# MCU.net
KiCad netlist of a schematic drawn in Altium Designer
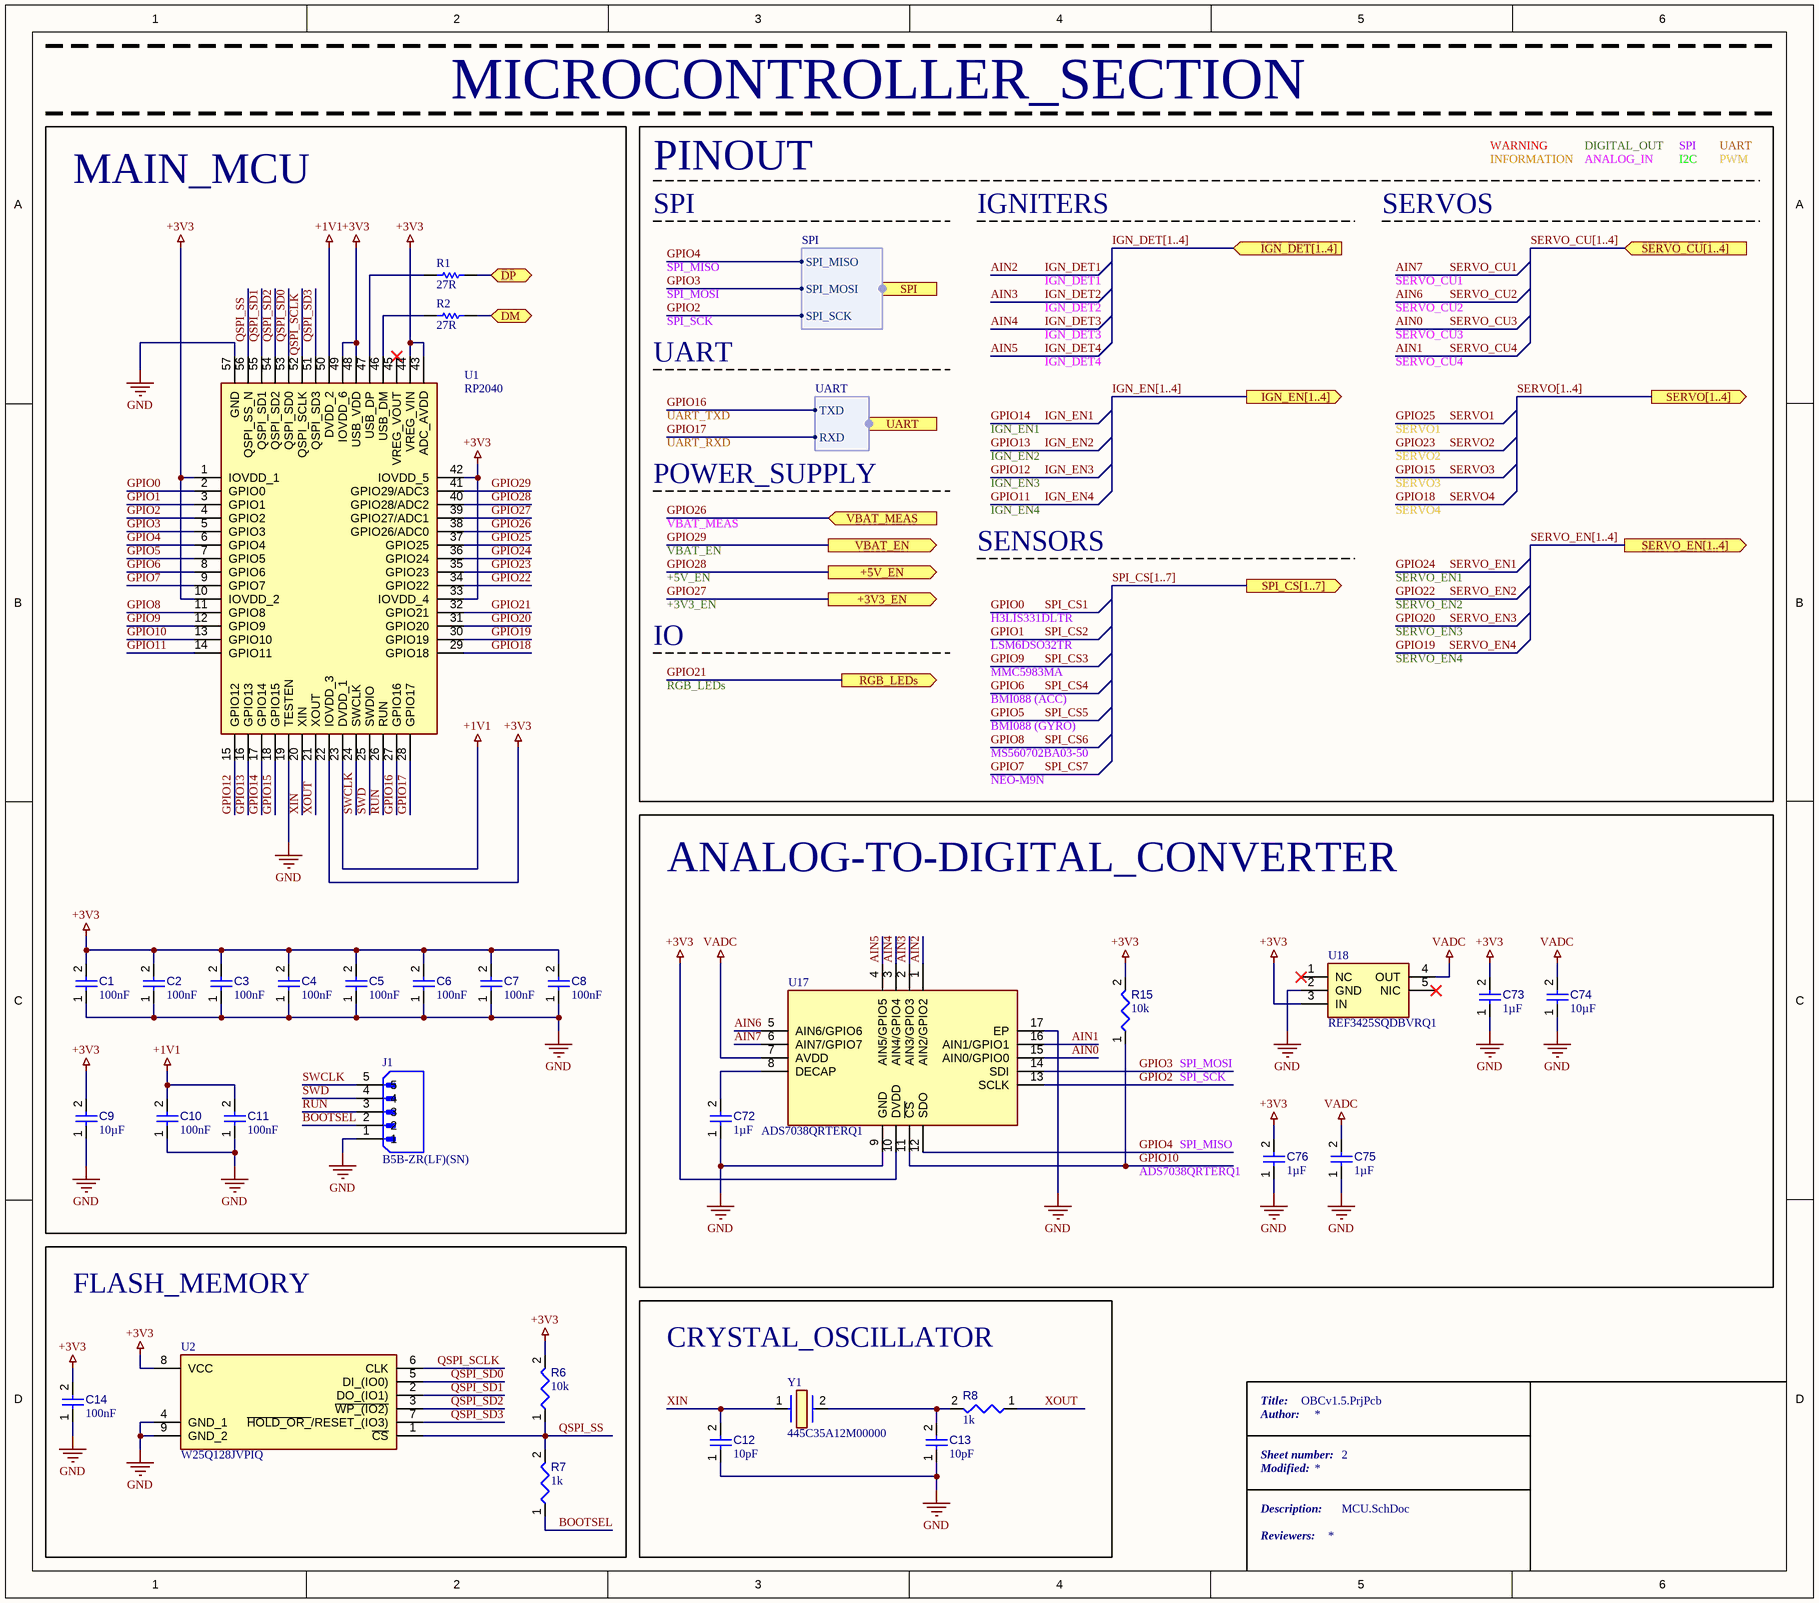
[diagram p0: MCU.SchDoc]

(export (version "E")
  (design (tool "Eeschema 10.0.6"))
  (components
    (comp (ref "C1")
      (value "100nF")
      (footprint "CAPC0402(1005)60_L")
      (description "Chip Capacitor, 100nF +/-20%, 10V, 0402, Thickness 0.6 mm")
      (fields (field (name "TOLERANCE") "20%") (field (name "Comment") "Capacitor 100nF +/-20% 10V 0402"))
      (libsource (lib "PWr in Space team") (part "CAP-NP-2"))
    )
    (comp (ref "C2")
      (value "100nF")
      (footprint "CAPC0402(1005)60_L")
      (description "Chip Capacitor, 100nF +/-20%, 10V, 0402, Thickness 0.6 mm")
      (fields (field (name "TOLERANCE") "20%") (field (name "Comment") "Capacitor 100nF +/-20% 10V 0402"))
      (libsource (lib "PWr in Space team") (part "CAP-NP-2"))
    )
    (comp (ref "C3")
      (value "100nF")
      (footprint "CAPC0402(1005)60_L")
      (description "Chip Capacitor, 100nF +/-20%, 10V, 0402, Thickness 0.6 mm")
      (fields (field (name "TOLERANCE") "20%") (field (name "Comment") "Capacitor 100nF +/-20% 10V 0402"))
      (libsource (lib "PWr in Space team") (part "CAP-NP-2"))
    )
    (comp (ref "C4")
      (value "100nF")
      (footprint "CAPC0402(1005)60_L")
      (description "Chip Capacitor, 100nF +/-20%, 10V, 0402, Thickness 0.6 mm")
      (fields (field (name "TOLERANCE") "20%") (field (name "Comment") "Capacitor 100nF +/-20% 10V 0402"))
      (libsource (lib "PWr in Space team") (part "CAP-NP-2"))
    )
    (comp (ref "C5")
      (value "100nF")
      (footprint "CAPC0402(1005)60_L")
      (description "Chip Capacitor, 100nF +/-20%, 10V, 0402, Thickness 0.6 mm")
      (fields (field (name "TOLERANCE") "20%") (field (name "Comment") "Capacitor 100nF +/-20% 10V 0402"))
      (libsource (lib "PWr in Space team") (part "CAP-NP-2"))
    )
    (comp (ref "C6")
      (value "100nF")
      (footprint "CAPC0402(1005)60_L")
      (description "Chip Capacitor, 100nF +/-20%, 10V, 0402, Thickness 0.6 mm")
      (fields (field (name "TOLERANCE") "20%") (field (name "Comment") "Capacitor 100nF +/-20% 10V 0402"))
      (libsource (lib "PWr in Space team") (part "CAP-NP-2"))
    )
    (comp (ref "C7")
      (value "100nF")
      (footprint "CAPC0402(1005)60_L")
      (description "Chip Capacitor, 100nF +/-20%, 10V, 0402, Thickness 0.6 mm")
      (fields (field (name "TOLERANCE") "20%") (field (name "Comment") "Capacitor 100nF +/-20% 10V 0402"))
      (libsource (lib "PWr in Space team") (part "CAP-NP-2"))
    )
    (comp (ref "C8")
      (value "100nF")
      (footprint "CAPC0402(1005)60_L")
      (description "Chip Capacitor, 100nF +/-20%, 10V, 0402, Thickness 0.6 mm")
      (fields (field (name "TOLERANCE") "20%") (field (name "Comment") "Capacitor 100nF +/-20% 10V 0402"))
      (libsource (lib "PWr in Space team") (part "CAP-NP-2"))
    )
    (comp (ref "C9")
      (value "10µF")
      (footprint "CAPC3216X180X50NL20T25")
      (description "Chip Capacitor, 10 uF, +/- 10%, 16 V, 1206 (3216 Metric)")
      (fields (field (name "TOLERANCE") "10%") (field (name "Comment") "Capacitor 10 uF +/- 10% 16 V 1206"))
      (libsource (lib "PWr in Space team") (part "CAP-NP-2"))
    )
    (comp (ref "C10")
      (value "100nF")
      (footprint "CAPC0402(1005)60_L")
      (description "Chip Capacitor, 100nF +/-20%, 10V, 0402, Thickness 0.6 mm")
      (fields (field (name "TOLERANCE") "20%") (field (name "Comment") "Capacitor 100nF +/-20% 10V 0402"))
      (libsource (lib "PWr in Space team") (part "CAP-NP-2"))
    )
    (comp (ref "C11")
      (value "100nF")
      (footprint "CAPC0402(1005)60_L")
      (description "Chip Capacitor, 100nF +/-20%, 10V, 0402, Thickness 0.6 mm")
      (fields (field (name "TOLERANCE") "20%") (field (name "Comment") "Capacitor 100nF +/-20% 10V 0402"))
      (libsource (lib "PWr in Space team") (part "CAP-NP-2"))
    )
    (comp (ref "C12")
      (value "10pF")
      (footprint "CAPC1005X55X30LL05T10")
      (description "Chip Capacitor, 10 pF, +/- 0.25 pF, 50 V, 0402 (1005 Metric)")
      (fields
        (field (name "TOLERANCE") "0.25%")
        (field (name "Comment") "Capacitor 10 pF +/- 0.25 pF 50 V 0402")
      )
      (libsource (lib "PWr in Space team") (part "CAP-NP-2"))
    )
    (comp (ref "C13")
      (value "10pF")
      (footprint "CAPC1005X55X30LL05T10")
      (description "Chip Capacitor, 10 pF, +/- 0.25 pF, 50 V, 0402 (1005 Metric)")
      (fields
        (field (name "TOLERANCE") "0.25%")
        (field (name "Comment") "Capacitor 10 pF +/- 0.25 pF 50 V 0402")
      )
      (libsource (lib "PWr in Space team") (part "CAP-NP-2"))
    )
    (comp (ref "C14")
      (value "100nF")
      (footprint "CAPC0402(1005)60_L")
      (description "Chip Capacitor, 100nF +/-20%, 10V, 0402, Thickness 0.6 mm")
      (fields (field (name "TOLERANCE") "20%") (field (name "Comment") "Capacitor 100nF +/-20% 10V 0402"))
      (libsource (lib "PWr in Space team") (part "CAP-NP-2"))
    )
    (comp (ref "C72")
      (value "1µF")
      (footprint "CAPC0402(1005)60_L")
      (description "Chip Capacitor, 1µF +/-20%, 10V, 0402, Thickness 0.6 mm")
      (fields (field (name "TOLERANCE") "10%") (field (name "Comment") "Capacitor 1µF +/-20% 10V 0402"))
      (libsource (lib "PWr in Space team") (part "CAP-NP-2"))
    )
    (comp (ref "C73")
      (value "1µF")
      (footprint "CAPC0402(1005)60_L")
      (description "Chip Capacitor, 1µF +/-20%, 10V, 0402, Thickness 0.6 mm")
      (fields (field (name "TOLERANCE") "10%") (field (name "Comment") "Capacitor 1µF +/-20% 10V 0402"))
      (libsource (lib "PWr in Space team") (part "CAP-NP-2"))
    )
    (comp (ref "C74")
      (value "10µF")
      (footprint "CAPC0603(1608)100_L")
      (description "Chip Capacitor, 10µF +/-20%, 10V, 0603, Thickness 1 mm")
      (fields (field (name "TOLERANCE") "10%") (field (name "Comment") "Capacitor 10µF +/-20% 10V 0603"))
      (libsource (lib "PWr in Space team") (part "CAP-NP-2"))
    )
    (comp (ref "C75")
      (value "1µF")
      (footprint "CAPC0402(1005)60_L")
      (description "Chip Capacitor, 1µF +/-20%, 10V, 0402, Thickness 0.6 mm")
      (fields (field (name "TOLERANCE") "10%") (field (name "Comment") "Capacitor 1µF +/-20% 10V 0402"))
      (libsource (lib "PWr in Space team") (part "CAP-NP-2"))
    )
    (comp (ref "C76")
      (value "1µF")
      (footprint "CAPC0402(1005)60_L")
      (description "Chip Capacitor, 1µF +/-20%, 10V, 0402, Thickness 0.6 mm")
      (fields (field (name "TOLERANCE") "10%") (field (name "Comment") "Capacitor 1µF +/-20% 10V 0402"))
      (libsource (lib "PWr in Space team") (part "CAP-NP-2"))
    )
    (comp (ref "J1")
      (value "B5B-ZR(LF)(SN)")
      (footprint "JST_B5B-ZR(LF)(SN)")
      (fields (field (name "MF") "{'manufacturer': u'JST'}"))
      (libsource (lib "SnapEDA_Library") (part "B5B-ZR(LF)(SN)"))
    )
    (comp (ref "R1")
      (value "27R")
      (footprint "RESC1005X40X25NL05T05")
      (fields (field (name "MANUFACTURER") "Vishay Dale") (field (name "PART NUMBER") "CRCW040227R0JNED"))
      (libsource (lib "Altium Content Vault") (part "RES"))
    )
    (comp (ref "R2")
      (value "27R")
      (footprint "RESC1005X40X25NL05T05")
      (fields (field (name "MANUFACTURER") "Vishay Dale") (field (name "PART NUMBER") "CRCW040227R0JNED"))
      (libsource (lib "Altium Content Vault") (part "RES"))
    )
    (comp (ref "R6")
      (value "10k")
      (footprint "RESC0402(1005)_L")
      (description "Chip Resistor, 10 kOhms, +/-1 %, 63 mW, -55 to 125 degC, 0402")
      (fields (field (name "POWER") "63mW") (field (name "TOLERANCE") "1%"))
      (libsource (lib "PWr in Space team") (part "RES-2"))
    )
    (comp (ref "R7")
      (value "1k")
      (footprint "RESC0402(1005)_L")
      (description "Chip Resistor, 1 kOhms, +/-5 %, 63 mW, -55 to 155 degC, 0402")
      (fields (field (name "TOLERANCE") "5%") (field (name "POWER") "63mW"))
      (libsource (lib "PWr in Space team") (part "RES-2"))
    )
    (comp (ref "R8")
      (value "1k")
      (footprint "RESC0402(1005)_L")
      (description "Chip Resistor, 1 kOhms, +/-5 %, 63 mW, -55 to 155 degC, 0402")
      (fields (field (name "TOLERANCE") "5%") (field (name "POWER") "63mW"))
      (libsource (lib "PWr in Space team") (part "RES-2"))
    )
    (comp (ref "R15")
      (value "10k")
      (footprint "RESC0402(1005)_L")
      (description "Chip Resistor, 10 kOhms, +/-1 %, 63 mW, -55 to 125 degC, 0402")
      (fields (field (name "POWER") "63mW") (field (name "TOLERANCE") "1%"))
      (libsource (lib "PWr in Space team") (part "RES-2"))
    )
    (comp (ref "U1")
      (value "RP2040")
      (footprint "QFN40P700X700X90-57N-D")
      (description "Integrated Circuit")
      (fields
        (field (name "MANUFACTURER_PART_NUMBER") "RPI Chip RP2040-10-10")
        (field (name "MOUSER PART NUMBER") "358-RP2040CHIP-10-10")
      )
      (libsource (lib "PWr in Space team") (part "RPI_Chip_RP2040-10-10"))
    )
    (comp (ref "U2")
      (value "W25Q128JVPIQ")
      (footprint "SamacSys:SON127P600X500X80-9N-D")
      (description "Integrated Circuit")
      (fields (field (name "MOUSER PART NUMBER") "454-W25Q128JVPIQ"))
      (libsource (lib "*") (part "W25Q128JVPIQ"))
    )
    (comp (ref "U17")
      (value "ADS7038QRTERQ1")
      (footprint "SamacSys:QFN50P300X300X80-17N-D")
      (description "Integrated Circuit")
      (fields (field (name "MOUSER PART NUMBER") "595-ADS7038QRTERQ1"))
      (libsource (lib "*") (part "ADS7038QRTERQ1"))
    )
    (comp (ref "U18")
      (value "REF3425SQDBVRQ1")
      (footprint "SamacSys:SOT95P280X145-5N")
      (description "Integrated Circuit")
      (fields (field (name "MOUSER PART NUMBER") "595-REF3425SQDBVRQ1"))
      (libsource (lib "*") (part "REF3425SQDBVRQ1"))
    )
    (comp (ref "Y1")
      (value "445C35A12M00000")
      (footprint "SamacSys:445I23D24M00000")
      (description "Crystal or Oscillator")
      (fields
        (field (name "MANUFACTURER_PART_NUMBER") "445I23D12M00000")
        (field (name "MOUSER PART NUMBER") "774-445I23D12M00000")
      )
      (libsource (lib "*") (part "445I23D12M00000"))
    )
  )
  (nets
    (net (code "3") (name "+1V1") (class "Default")
      (node (ref "C10") (pin "2") (pinfunction "2_2") (pintype "passive"))
      (node (ref "C11") (pin "2") (pinfunction "2_2") (pintype "passive"))
      (node (ref "U1") (pin "23") (pinfunction "DVDD_1_23") (pintype "passive"))
      (node (ref "U1") (pin "50") (pinfunction "DVDD_2_50") (pintype "passive"))
    )
    (net (code "4") (name "+3V3") (class "Default")
      (node (ref "C1") (pin "2") (pinfunction "2_2") (pintype "passive"))
      (node (ref "C14") (pin "2") (pinfunction "2_2") (pintype "passive"))
      (node (ref "C2") (pin "2") (pinfunction "2_2") (pintype "passive"))
      (node (ref "C3") (pin "2") (pinfunction "2_2") (pintype "passive"))
      (node (ref "C4") (pin "2") (pinfunction "2_2") (pintype "passive"))
      (node (ref "C5") (pin "2") (pinfunction "2_2") (pintype "passive"))
      (node (ref "C6") (pin "2") (pinfunction "2_2") (pintype "passive"))
      (node (ref "C7") (pin "2") (pinfunction "2_2") (pintype "passive"))
      (node (ref "C73") (pin "2") (pinfunction "2_2") (pintype "passive"))
      (node (ref "C76") (pin "2") (pinfunction "2_2") (pintype "passive"))
      (node (ref "C8") (pin "2") (pinfunction "2_2") (pintype "passive"))
      (node (ref "C9") (pin "2") (pinfunction "2_2") (pintype "passive"))
      (node (ref "R15") (pin "2") (pinfunction "2_2") (pintype "passive"))
      (node (ref "R6") (pin "2") (pinfunction "2_2") (pintype "passive"))
      (node (ref "U1") (pin "1") (pinfunction "IOVDD_1_1") (pintype "passive"))
      (node (ref "U1") (pin "10") (pinfunction "IOVDD_2_10") (pintype "passive"))
      (node (ref "U1") (pin "22") (pinfunction "IOVDD_3_22") (pintype "passive"))
      (node (ref "U1") (pin "33") (pinfunction "IOVDD_4_33") (pintype "passive"))
      (node (ref "U1") (pin "42") (pinfunction "IOVDD_5_42") (pintype "passive"))
      (node (ref "U1") (pin "43") (pinfunction "ADC_AVDD_43") (pintype "passive"))
      (node (ref "U1") (pin "44") (pinfunction "VREG_VIN_44") (pintype "passive"))
      (node (ref "U1") (pin "48") (pinfunction "USB_VDD_48") (pintype "passive"))
      (node (ref "U1") (pin "49") (pinfunction "IOVDD_6_49") (pintype "passive"))
      (node (ref "U17") (pin "10") (pinfunction "DVDD_10") (pintype "passive"))
      (node (ref "U18") (pin "3") (pinfunction "IN_3") (pintype "passive"))
      (node (ref "U2") (pin "8") (pinfunction "VCC_8") (pintype "passive"))
    )
    (net (code "5") (name "/BOOTSEL") (class "Default")
      (node (ref "J1") (pin "2") (pinfunction "2_2") (pintype "passive"))
      (node (ref "R7") (pin "1") (pinfunction "1_1") (pintype "passive"))
    )
    (net (code "6") (name "/DM") (class "Default")
      (node (ref "R2") (pin "2") (pinfunction "2_2") (pintype "passive"))
    )
    (net (code "7") (name "/DP") (class "Default")
      (node (ref "R1") (pin "2") (pinfunction "2_2") (pintype "passive"))
    )
    (net (code "8") (name "/GPIO2") (class "Default")
      (node (ref "U1") (pin "4") (pinfunction "GPIO2_4") (pintype "passive"))
      (node (ref "U17") (pin "13") (pinfunction "SCLK_13") (pintype "passive"))
    )
    (net (code "9") (name "/GPIO3") (class "Default")
      (node (ref "U1") (pin "5") (pinfunction "GPIO3_5") (pintype "passive"))
      (node (ref "U17") (pin "14") (pinfunction "SDI_14") (pintype "passive"))
    )
    (net (code "10") (name "/GPIO4") (class "Default")
      (node (ref "U1") (pin "6") (pinfunction "GPIO4_6") (pintype "passive"))
      (node (ref "U17") (pin "12") (pinfunction "SDO_12") (pintype "passive"))
    )
    (net (code "11") (name "/GPIO10") (class "Default")
      (node (ref "R15") (pin "1") (pinfunction "1_1") (pintype "passive"))
      (node (ref "U1") (pin "13") (pinfunction "GPIO10_13") (pintype "passive"))
      (node (ref "U17") (pin "11") (pinfunction "~{CS}_11") (pintype "passive"))
    )
    (net (code "12") (name "/GPIO16") (class "Default")
      (node (ref "U1") (pin "27") (pinfunction "GPIO16_27") (pintype "passive"))
    )
    (net (code "13") (name "/GPIO17") (class "Default")
      (node (ref "U1") (pin "28") (pinfunction "GPIO17_28") (pintype "passive"))
    )
    (net (code "14") (name "/GPIO21") (class "Default")
      (node (ref "U1") (pin "32") (pinfunction "GPIO21_32") (pintype "passive"))
    )
    (net (code "15") (name "/GPIO26") (class "Default")
      (node (ref "U1") (pin "38") (pinfunction "GPIO26/ADC0_38") (pintype "passive"))
    )
    (net (code "16") (name "/GPIO27") (class "Default")
      (node (ref "U1") (pin "39") (pinfunction "GPIO27/ADC1_39") (pintype "passive"))
    )
    (net (code "17") (name "/GPIO28") (class "Default")
      (node (ref "U1") (pin "40") (pinfunction "GPIO28/ADC2_40") (pintype "passive"))
    )
    (net (code "18") (name "/GPIO29") (class "Default")
      (node (ref "U1") (pin "41") (pinfunction "GPIO29/ADC3_41") (pintype "passive"))
    )
    (net (code "19") (name "/IGN_DET1") (class "Default")
      (node (ref "U17") (pin "1") (pinfunction "AIN2/GPIO2_1") (pintype "passive"))
    )
    (net (code "20") (name "/IGN_DET2") (class "Default")
      (node (ref "U17") (pin "2") (pinfunction "AIN3/GPIO3_2") (pintype "passive"))
    )
    (net (code "21") (name "/IGN_DET3") (class "Default")
      (node (ref "U17") (pin "3") (pinfunction "AIN4/GPIO4_3") (pintype "passive"))
    )
    (net (code "22") (name "/IGN_DET4") (class "Default")
      (node (ref "U17") (pin "4") (pinfunction "AIN5/GPIO5_4") (pintype "passive"))
    )
    (net (code "24") (name "/IGN_EN1") (class "Default")
      (node (ref "U1") (pin "17") (pinfunction "GPIO14_17") (pintype "passive"))
    )
    (net (code "25") (name "/IGN_EN2") (class "Default")
      (node (ref "U1") (pin "16") (pinfunction "GPIO13_16") (pintype "passive"))
    )
    (net (code "26") (name "/IGN_EN3") (class "Default")
      (node (ref "U1") (pin "15") (pinfunction "GPIO12_15") (pintype "passive"))
    )
    (net (code "27") (name "/IGN_EN4") (class "Default")
      (node (ref "U1") (pin "14") (pinfunction "GPIO11_14") (pintype "passive"))
    )
    (net (code "29") (name "/QSPI_SCLK") (class "Default")
      (node (ref "U1") (pin "52") (pinfunction "QSPI_SCLK_52") (pintype "passive"))
      (node (ref "U2") (pin "6") (pinfunction "CLK_6") (pintype "passive"))
    )
    (net (code "30") (name "/QSPI_SD0") (class "Default")
      (node (ref "U1") (pin "53") (pinfunction "QSPI_SD0_53") (pintype "passive"))
      (node (ref "U2") (pin "5") (pinfunction "DI_(IO0)_5") (pintype "passive"))
    )
    (net (code "31") (name "/QSPI_SD1") (class "Default")
      (node (ref "U1") (pin "55") (pinfunction "QSPI_SD1_55") (pintype "passive"))
      (node (ref "U2") (pin "2") (pinfunction "DO_(IO1)_2") (pintype "passive"))
    )
    (net (code "32") (name "/QSPI_SD2") (class "Default")
      (node (ref "U1") (pin "54") (pinfunction "QSPI_SD2_54") (pintype "passive"))
      (node (ref "U2") (pin "3") (pinfunction "~{WP_(IO2)}_3") (pintype "passive"))
    )
    (net (code "33") (name "/QSPI_SD3") (class "Default")
      (node (ref "U1") (pin "51") (pinfunction "QSPI_SD3_51") (pintype "passive"))
      (node (ref "U2") (pin "7") (pinfunction "~{HOLD_OR_}/RESET_(IO3)_7") (pintype "passive"))
    )
    (net (code "34") (name "/QSPI_SS") (class "Default")
      (node (ref "R6") (pin "1") (pinfunction "1_1") (pintype "passive"))
      (node (ref "R7") (pin "2") (pinfunction "2_2") (pintype "passive"))
      (node (ref "U1") (pin "56") (pinfunction "QSPI_SS_N_56") (pintype "passive"))
      (node (ref "U2") (pin "1") (pinfunction "~{CS}_1") (pintype "passive"))
    )
    (net (code "35") (name "/RUN") (class "Default")
      (node (ref "J1") (pin "3") (pinfunction "3_3") (pintype "passive"))
      (node (ref "U1") (pin "26") (pinfunction "RUN_26") (pintype "passive"))
    )
    (net (code "36") (name "/SERVO1") (class "Default")
      (node (ref "U1") (pin "37") (pinfunction "GPIO25_37") (pintype "passive"))
    )
    (net (code "37") (name "/SERVO2") (class "Default")
      (node (ref "U1") (pin "35") (pinfunction "GPIO23_35") (pintype "passive"))
    )
    (net (code "38") (name "/SERVO3") (class "Default")
      (node (ref "U1") (pin "18") (pinfunction "GPIO15_18") (pintype "passive"))
    )
    (net (code "39") (name "/SERVO4") (class "Default")
      (node (ref "U1") (pin "29") (pinfunction "GPIO18_29") (pintype "passive"))
    )
    (net (code "41") (name "/SERVO_CU1") (class "Default")
      (node (ref "U17") (pin "6") (pinfunction "AIN7/GPIO7_6") (pintype "passive"))
    )
    (net (code "42") (name "/SERVO_CU2") (class "Default")
      (node (ref "U17") (pin "5") (pinfunction "AIN6/GPIO6_5") (pintype "passive"))
    )
    (net (code "43") (name "/SERVO_CU3") (class "Default")
      (node (ref "U17") (pin "15") (pinfunction "AIN0/GPIO0_15") (pintype "passive"))
    )
    (net (code "44") (name "/SERVO_CU4") (class "Default")
      (node (ref "U17") (pin "16") (pinfunction "AIN1/GPIO1_16") (pintype "passive"))
    )
    (net (code "46") (name "/SERVO_EN1") (class "Default")
      (node (ref "U1") (pin "36") (pinfunction "GPIO24_36") (pintype "passive"))
    )
    (net (code "47") (name "/SERVO_EN2") (class "Default")
      (node (ref "U1") (pin "34") (pinfunction "GPIO22_34") (pintype "passive"))
    )
    (net (code "48") (name "/SERVO_EN3") (class "Default")
      (node (ref "U1") (pin "31") (pinfunction "GPIO20_31") (pintype "passive"))
    )
    (net (code "49") (name "/SERVO_EN4") (class "Default")
      (node (ref "U1") (pin "30") (pinfunction "GPIO19_30") (pintype "passive"))
    )
    (net (code "51") (name "/SPI_CS1") (class "Default")
      (node (ref "U1") (pin "2") (pinfunction "GPIO0_2") (pintype "passive"))
    )
    (net (code "52") (name "/SPI_CS2") (class "Default")
      (node (ref "U1") (pin "3") (pinfunction "GPIO1_3") (pintype "passive"))
    )
    (net (code "53") (name "/SPI_CS3") (class "Default")
      (node (ref "U1") (pin "12") (pinfunction "GPIO9_12") (pintype "passive"))
    )
    (net (code "54") (name "/SPI_CS4") (class "Default")
      (node (ref "U1") (pin "8") (pinfunction "GPIO6_8") (pintype "passive"))
    )
    (net (code "55") (name "/SPI_CS5") (class "Default")
      (node (ref "U1") (pin "7") (pinfunction "GPIO5_7") (pintype "passive"))
    )
    (net (code "56") (name "/SPI_CS6") (class "Default")
      (node (ref "U1") (pin "11") (pinfunction "GPIO8_11") (pintype "passive"))
    )
    (net (code "57") (name "/SPI_CS7") (class "Default")
      (node (ref "U1") (pin "9") (pinfunction "GPIO7_9") (pintype "passive"))
    )
    (net (code "59") (name "/SWCLK") (class "Default")
      (node (ref "J1") (pin "5") (pinfunction "5_5") (pintype "passive"))
      (node (ref "U1") (pin "24") (pinfunction "SWCLK_24") (pintype "passive"))
    )
    (net (code "60") (name "/SWD") (class "Default")
      (node (ref "J1") (pin "4") (pinfunction "4_4") (pintype "passive"))
      (node (ref "U1") (pin "25") (pinfunction "SWDIO_25") (pintype "passive"))
    )
    (net (code "61") (name "/XIN") (class "Default")
      (node (ref "C12") (pin "2") (pinfunction "2_2") (pintype "passive"))
      (node (ref "U1") (pin "20") (pinfunction "XIN_20") (pintype "passive"))
      (node (ref "Y1") (pin "1") (pinfunction "1_1") (pintype "passive"))
    )
    (net (code "62") (name "/XOUT") (class "Default")
      (node (ref "R8") (pin "1") (pinfunction "1_1") (pintype "passive"))
      (node (ref "U1") (pin "21") (pinfunction "XOUT_21") (pintype "passive"))
    )
    (net (code "65") (name "GND") (class "Default")
      (node (ref "C1") (pin "1") (pinfunction "1_1") (pintype "passive"))
      (node (ref "C10") (pin "1") (pinfunction "1_1") (pintype "passive"))
      (node (ref "C11") (pin "1") (pinfunction "1_1") (pintype "passive"))
      (node (ref "C12") (pin "1") (pinfunction "1_1") (pintype "passive"))
      (node (ref "C13") (pin "1") (pinfunction "1_1") (pintype "passive"))
      (node (ref "C14") (pin "1") (pinfunction "1_1") (pintype "passive"))
      (node (ref "C2") (pin "1") (pinfunction "1_1") (pintype "passive"))
      (node (ref "C3") (pin "1") (pinfunction "1_1") (pintype "passive"))
      (node (ref "C4") (pin "1") (pinfunction "1_1") (pintype "passive"))
      (node (ref "C5") (pin "1") (pinfunction "1_1") (pintype "passive"))
      (node (ref "C6") (pin "1") (pinfunction "1_1") (pintype "passive"))
      (node (ref "C7") (pin "1") (pinfunction "1_1") (pintype "passive"))
      (node (ref "C72") (pin "1") (pinfunction "1_1") (pintype "passive"))
      (node (ref "C73") (pin "1") (pinfunction "1_1") (pintype "passive"))
      (node (ref "C74") (pin "1") (pinfunction "1_1") (pintype "passive"))
      (node (ref "C75") (pin "1") (pinfunction "1_1") (pintype "passive"))
      (node (ref "C76") (pin "1") (pinfunction "1_1") (pintype "passive"))
      (node (ref "C8") (pin "1") (pinfunction "1_1") (pintype "passive"))
      (node (ref "C9") (pin "1") (pinfunction "1_1") (pintype "passive"))
      (node (ref "J1") (pin "1") (pinfunction "1_1") (pintype "passive"))
      (node (ref "U1") (pin "19") (pinfunction "TESTEN_19") (pintype "passive"))
      (node (ref "U1") (pin "57") (pinfunction "GND_57") (pintype "passive"))
      (node (ref "U17") (pin "17") (pinfunction "EP_17") (pintype "passive"))
      (node (ref "U17") (pin "9") (pinfunction "GND_9") (pintype "passive"))
      (node (ref "U18") (pin "2") (pinfunction "GND_2") (pintype "passive"))
      (node (ref "U2") (pin "4") (pinfunction "GND_1_4") (pintype "passive"))
      (node (ref "U2") (pin "9") (pinfunction "GND_2_9") (pintype "passive"))
    )
    (net (code "66") (name "Net-(C13-Pad2)") (class "Default")
      (node (ref "C13") (pin "2") (pinfunction "2_2") (pintype "passive"))
      (node (ref "R8") (pin "2") (pinfunction "2_2") (pintype "passive"))
      (node (ref "Y1") (pin "2") (pinfunction "2_2") (pintype "passive"))
    )
    (net (code "67") (name "Net-(U1-USB_DM)") (class "Default")
      (node (ref "R2") (pin "1") (pinfunction "1_1") (pintype "passive"))
      (node (ref "U1") (pin "46") (pinfunction "USB_DM_46") (pintype "passive"))
    )
    (net (code "68") (name "Net-(U1-USB_DP)") (class "Default")
      (node (ref "R1") (pin "1") (pinfunction "1_1") (pintype "passive"))
      (node (ref "U1") (pin "47") (pinfunction "USB_DP_47") (pintype "passive"))
    )
    (net (code "69") (name "Net-(U17-DECAP)") (class "Default")
      (node (ref "C72") (pin "2") (pinfunction "2_2") (pintype "passive"))
      (node (ref "U17") (pin "8") (pinfunction "DECAP_8") (pintype "passive"))
    )
    (net (code "70") (name "VADC") (class "Default")
      (node (ref "C74") (pin "2") (pinfunction "2_2") (pintype "passive"))
      (node (ref "C75") (pin "2") (pinfunction "2_2") (pintype "passive"))
      (node (ref "U17") (pin "7") (pinfunction "AVDD_7") (pintype "passive"))
      (node (ref "U18") (pin "4") (pinfunction "OUT_4") (pintype "passive"))
    )
    (net (code "71") (name "unconnected-(U1-VREG_VOUT-Pad45)") (class "Default")
      (node (ref "U1") (pin "45") (pinfunction "VREG_VOUT_45") (pintype "passive+no_connect"))
    )
    (net (code "72") (name "unconnected-(U18-NC-Pad1)") (class "Default")
      (node (ref "U18") (pin "1") (pinfunction "NC_1") (pintype "passive+no_connect"))
    )
    (net (code "73") (name "unconnected-(U18-NIC-Pad5)") (class "Default")
      (node (ref "U18") (pin "5") (pinfunction "NIC_5") (pintype "passive+no_connect"))
    )
  )
)
